# fixture.net
KiCad netlist of a schematic drawn in EAGLE
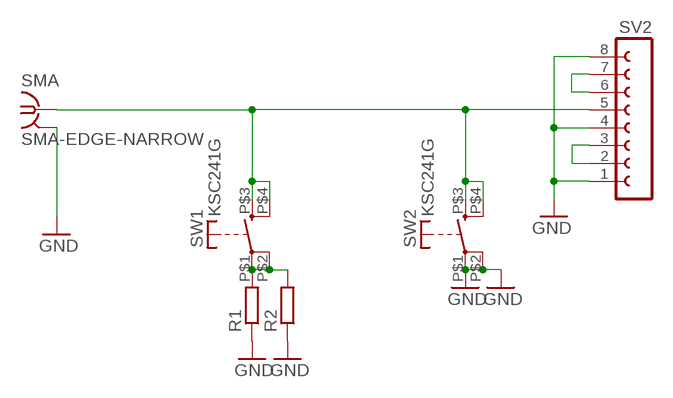
[diagram p0: schematic, sheet 1]

(export (version "E")
  (design (tool "Eeschema 10.0.6"))
  (components
    (comp (ref "R1")
      (value "R-EU_M0805")
      (footprint "eagle-import:M0805")
      (libsource (lib "eagle-import") (part "R-EU_M0805"))
    )
    (comp (ref "R2")
      (value "R-EU_M0805")
      (footprint "eagle-import:M0805")
      (libsource (lib "eagle-import") (part "R-EU_M0805"))
    )
    (comp (ref "SMA")
      (value "SMA-EDGE-NARROW")
      (footprint "eagle-import:SMD-EDGE-NARROW")
      (libsource (lib "eagle-import") (part "SMA-EDGE-NARROW"))
    )
    (comp (ref "SV2")
      (value "FE08-1")
      (footprint "eagle-import:FE08")
      (libsource (lib "eagle-import") (part "FE08-1"))
    )
    (comp (ref "SW1")
      (value "KSC241G")
      (footprint "eagle-import:KSC241G")
      (libsource (lib "eagle-import") (part "KSC241G"))
    )
    (comp (ref "SW2")
      (value "KSC241G")
      (footprint "eagle-import:KSC241G")
      (libsource (lib "eagle-import") (part "KSC241G"))
    )
  )
  (nets
    (net (code "1") (name "GND") (class "Default")
      (node (ref "R1") (pin "1") (pinfunction "1_1") (pintype "passive"))
      (node (ref "R2") (pin "1") (pinfunction "1_1") (pintype "passive"))
      (node (ref "SMA") (pin "G@1") (pinfunction "2_G@1") (pintype "passive"))
      (node (ref "SMA") (pin "G@2") (pinfunction "2_G@2") (pintype "passive"))
      (node (ref "SMA") (pin "G@3") (pinfunction "2_G@3") (pintype "passive"))
      (node (ref "SMA") (pin "G@4") (pinfunction "2_G@4") (pintype "passive"))
      (node (ref "SV2") (pin "1") (pinfunction "1_1") (pintype "passive"))
      (node (ref "SV2") (pin "4") (pinfunction "4_4") (pintype "passive"))
      (node (ref "SV2") (pin "8") (pinfunction "8_8") (pintype "passive"))
      (node (ref "SW2") (pin "P$1") (pinfunction "P_P$1") (pintype "passive"))
      (node (ref "SW2") (pin "P$2") (pinfunction "P_P$2") (pintype "passive"))
    )
    (net (code "2") (name "Net-(R1-Pad2)") (class "Default")
      (node (ref "R1") (pin "2") (pinfunction "2_2") (pintype "passive"))
      (node (ref "R2") (pin "2") (pinfunction "2_2") (pintype "passive"))
      (node (ref "SW1") (pin "P$1") (pinfunction "P_P$1") (pintype "passive"))
      (node (ref "SW1") (pin "P$2") (pinfunction "P_P$2") (pintype "passive"))
    )
    (net (code "3") (name "Net-(SMA-Pad1)") (class "Default")
      (node (ref "SMA") (pin "1") (pinfunction "1_1") (pintype "passive"))
      (node (ref "SV2") (pin "5") (pinfunction "5_5") (pintype "passive"))
      (node (ref "SW1") (pin "P$3") (pinfunction "S_P$3") (pintype "passive"))
      (node (ref "SW1") (pin "P$4") (pinfunction "S_P$4") (pintype "passive"))
      (node (ref "SW2") (pin "P$3") (pinfunction "S_P$3") (pintype "passive"))
      (node (ref "SW2") (pin "P$4") (pinfunction "S_P$4") (pintype "passive"))
    )
    (net (code "4") (name "Net-(SV2-Pad2)") (class "Default")
      (node (ref "SV2") (pin "2") (pinfunction "2_2") (pintype "passive"))
      (node (ref "SV2") (pin "3") (pinfunction "3_3") (pintype "passive"))
    )
    (net (code "5") (name "Net-(SV2-Pad6)") (class "Default")
      (node (ref "SV2") (pin "6") (pinfunction "6_6") (pintype "passive"))
      (node (ref "SV2") (pin "7") (pinfunction "7_7") (pintype "passive"))
    )
  )
)
